# main.net
KiCad netlist of a schematic drawn in Altium Designer
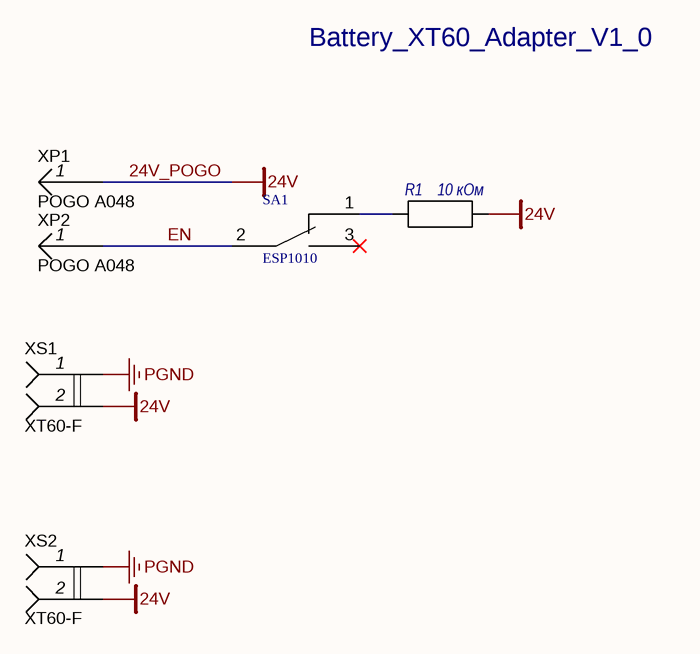
[diagram p0: main.SchDoc]

(export (version "E")
  (design (tool "Eeschema 10.0.6"))
  (components
    (comp (ref "R1")
      (value "10 кОм")
      (footprint "C0603R")
      (description "SMD 0603; 0,1; 1%; 10 кОм")
      (fields (field (name "PART NUMBER") "RC0603FR-0710KL") (field (name "POWER") "0,1"))
      (libsource (lib "Resistors") (part "RC0603FR-0710KL"))
    )
    (comp (ref "SA1")
      (value "ESP1010")
      (footprint "ESP1010")
      (description "SA")
      (fields (field (name "MANUFACTURER") "ECE"))
      (libsource (lib "Conectors") (part "ESP1010"))
    )
    (comp (ref "XP1")
      (value "POGO A048")
      (footprint "POGO_A048")
      (libsource (lib "Conectors") (part "POGO A048"))
    )
    (comp (ref "XP2")
      (value "POGO A048")
      (footprint "POGO_A048")
      (libsource (lib "Conectors") (part "POGO A048"))
    )
    (comp (ref "XS1")
      (value "XT60-F")
      (footprint "XT60-F")
      (fields (field (name "MANUFACTURER") "AMASS"))
      (libsource (lib "Conectors") (part "XT60-F"))
    )
    (comp (ref "XS2")
      (value "XT60-F")
      (footprint "XT60-F")
      (fields (field (name "MANUFACTURER") "AMASS"))
      (libsource (lib "Conectors") (part "XT60-F"))
    )
  )
  (nets
    (net (code "1") (name "/EN") (class "Default")
      (node (ref "SA1") (pin "2") (pinfunction "2_2") (pintype "passive"))
      (node (ref "XP2") (pin "1") (pinfunction "1_1") (pintype "passive"))
    )
    (net (code "2") (name "24V") (class "Default")
      (node (ref "R1") (pin "2") (pinfunction "2_2") (pintype "passive"))
      (node (ref "XP1") (pin "1") (pinfunction "1_1") (pintype "passive"))
      (node (ref "XS1") (pin "2") (pinfunction "2_2") (pintype "passive"))
      (node (ref "XS2") (pin "2") (pinfunction "2_2") (pintype "passive"))
    )
    (net (code "3") (name "Net-(R1-Pad1)") (class "Default")
      (node (ref "R1") (pin "1") (pinfunction "1_1") (pintype "passive"))
      (node (ref "SA1") (pin "1") (pinfunction "1_1") (pintype "passive"))
    )
    (net (code "4") (name "PGND") (class "Default")
      (node (ref "XS1") (pin "1") (pinfunction "1_1") (pintype "passive"))
      (node (ref "XS2") (pin "1") (pinfunction "1_1") (pintype "passive"))
    )
    (net (code "5") (name "unconnected-(SA1-Pad3)") (class "Default")
      (node (ref "SA1") (pin "3") (pintype "passive+no_connect"))
    )
  )
)
